# scoreboard.net
KiCad netlist of a schematic drawn in EAGLE
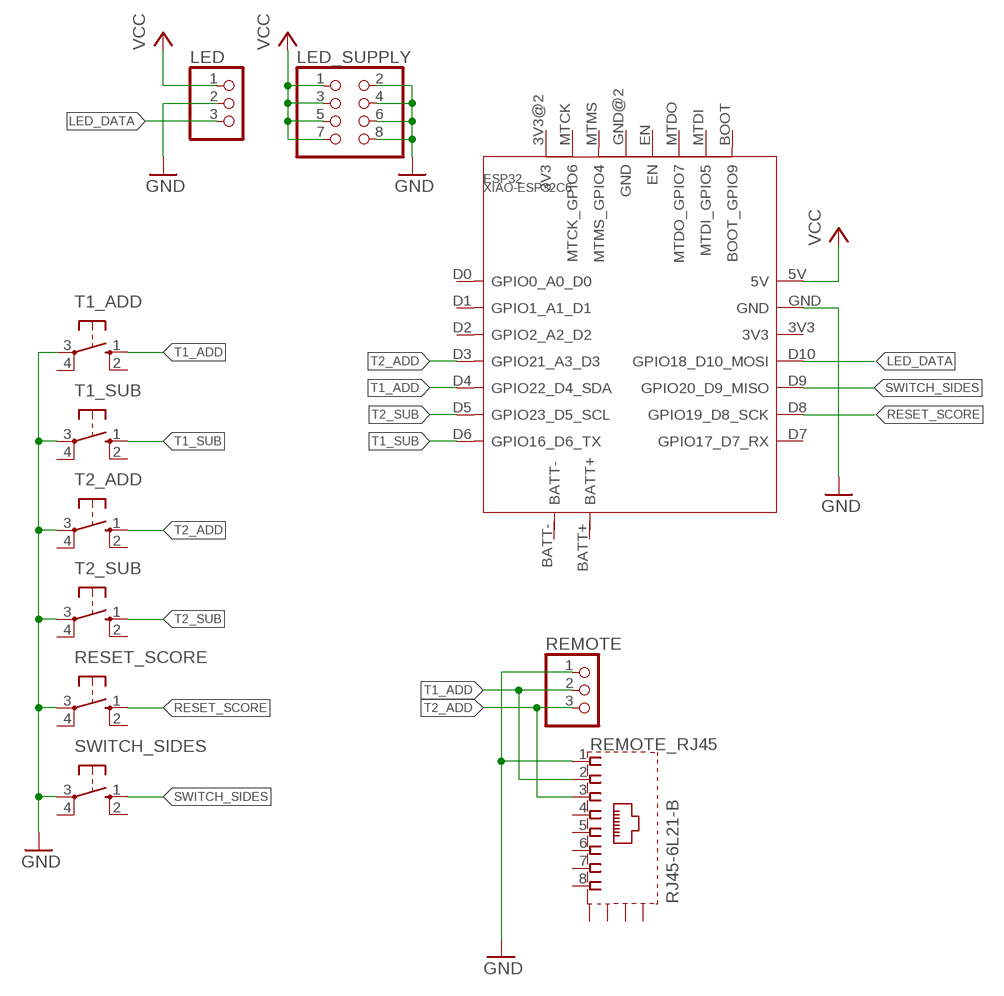
[diagram p0: schematic, sheet 1]

(export (version "E")
  (design (tool "Eeschema 10.0.6"))
  (components
    (comp (ref "ESP32")
      (value "XIAO-ESP32C6")
      (footprint "eagle-import:XIAO-ESP32C6-MODULE14P-2.54-21X17.8MM")
      (libsource (lib "eagle-import") (part "XIAO-ESP32C6"))
    )
    (comp (ref "LED")
      (value "PINHD-1X3")
      (footprint "eagle-import:1X03")
      (libsource (lib "eagle-import") (part "PINHD-1X3"))
    )
    (comp (ref "LED_SUPPLY")
      (value "PINHD-2X4")
      (footprint "eagle-import:2X04")
      (libsource (lib "eagle-import") (part "PINHD-2X4"))
    )
    (comp (ref "REMOTE")
      (value "PINHD-1X3")
      (footprint "eagle-import:1X03")
      (libsource (lib "eagle-import") (part "PINHD-1X3"))
    )
    (comp (ref "REMOTE_RJ45")
      (value "RJ45-6L21-B")
      (footprint "eagle-import:RJ45-SHIELD1")
      (libsource (lib "eagle-import") (part "RJ4521-B-6L"))
    )
    (comp (ref "RESET_SCORE")
      (value "10-XX")
      (footprint "eagle-import:B3F-10XX")
      (fields (field (name "MPN") "B3F-1000"))
      (libsource (lib "eagle-import") (part "10-XX"))
    )
    (comp (ref "SWITCH_SIDES")
      (value "10-XX")
      (footprint "eagle-import:B3F-10XX")
      (fields (field (name "MPN") "B3F-1000"))
      (libsource (lib "eagle-import") (part "10-XX"))
    )
    (comp (ref "T1_ADD")
      (value "10-XX")
      (footprint "eagle-import:B3F-10XX")
      (fields (field (name "MPN") "B3F-1000"))
      (libsource (lib "eagle-import") (part "10-XX"))
    )
    (comp (ref "T1_SUB")
      (value "10-XX")
      (footprint "eagle-import:B3F-10XX")
      (fields (field (name "MPN") "B3F-1000"))
      (libsource (lib "eagle-import") (part "10-XX"))
    )
    (comp (ref "T2_ADD")
      (value "10-XX")
      (footprint "eagle-import:B3F-10XX")
      (fields (field (name "MPN") "B3F-1000"))
      (libsource (lib "eagle-import") (part "10-XX"))
    )
    (comp (ref "T2_SUB")
      (value "10-XX")
      (footprint "eagle-import:B3F-10XX")
      (fields (field (name "MPN") "B3F-1000"))
      (libsource (lib "eagle-import") (part "10-XX"))
    )
  )
  (nets
    (net (code "1") (name "GND") (class "Default")
      (node (ref "ESP32") (pin "GND") (pinfunction "GND_GND") (pintype "bidirectional"))
      (node (ref "LED") (pin "2") (pinfunction "2_2") (pintype "passive"))
      (node (ref "LED_SUPPLY") (pin "2") (pinfunction "2_2") (pintype "passive"))
      (node (ref "LED_SUPPLY") (pin "4") (pinfunction "4_4") (pintype "passive"))
      (node (ref "LED_SUPPLY") (pin "6") (pinfunction "6_6") (pintype "passive"))
      (node (ref "LED_SUPPLY") (pin "8") (pinfunction "8_8") (pintype "passive"))
      (node (ref "REMOTE") (pin "1") (pinfunction "1_1") (pintype "passive"))
      (node (ref "REMOTE_RJ45") (pin "1") (pinfunction "1_1") (pintype "passive"))
      (node (ref "RESET_SCORE") (pin "3") (pinfunction "P_3") (pintype "passive"))
      (node (ref "SWITCH_SIDES") (pin "3") (pinfunction "P_3") (pintype "passive"))
      (node (ref "T1_ADD") (pin "3") (pinfunction "P_3") (pintype "passive"))
      (node (ref "T1_SUB") (pin "3") (pinfunction "P_3") (pintype "passive"))
      (node (ref "T2_ADD") (pin "3") (pinfunction "P_3") (pintype "passive"))
      (node (ref "T2_SUB") (pin "3") (pinfunction "P_3") (pintype "passive"))
    )
    (net (code "2") (name "LED_DATA") (class "Default")
      (node (ref "ESP32") (pin "D10") (pinfunction "GPIO18_D10_MOSI_D10") (pintype "bidirectional"))
      (node (ref "LED") (pin "3") (pinfunction "3_3") (pintype "passive"))
    )
    (net (code "3") (name "RESET_SCORE") (class "Default")
      (node (ref "ESP32") (pin "D8") (pinfunction "GPIO19_D8_SCK_D8") (pintype "bidirectional"))
      (node (ref "RESET_SCORE") (pin "1") (pinfunction "S_1") (pintype "passive"))
    )
    (net (code "4") (name "SWITCH_SIDES") (class "Default")
      (node (ref "ESP32") (pin "D9") (pinfunction "GPIO20_D9_MISO_D9") (pintype "bidirectional"))
      (node (ref "SWITCH_SIDES") (pin "1") (pinfunction "S_1") (pintype "passive"))
    )
    (net (code "5") (name "T1_ADD") (class "Default")
      (node (ref "ESP32") (pin "D4") (pinfunction "GPIO22_D4_SDA_D4") (pintype "bidirectional"))
      (node (ref "REMOTE") (pin "2") (pinfunction "2_2") (pintype "passive"))
      (node (ref "REMOTE_RJ45") (pin "2") (pinfunction "2_2") (pintype "passive"))
      (node (ref "T1_ADD") (pin "1") (pinfunction "S_1") (pintype "passive"))
    )
    (net (code "6") (name "T1_SUB") (class "Default")
      (node (ref "ESP32") (pin "D6") (pinfunction "GPIO16_D6_TX_D6") (pintype "bidirectional"))
      (node (ref "T1_SUB") (pin "1") (pinfunction "S_1") (pintype "passive"))
    )
    (net (code "7") (name "T2_ADD") (class "Default")
      (node (ref "ESP32") (pin "D3") (pinfunction "GPIO21_A3_D3_D3") (pintype "bidirectional"))
      (node (ref "REMOTE") (pin "3") (pinfunction "3_3") (pintype "passive"))
      (node (ref "REMOTE_RJ45") (pin "3") (pinfunction "3_3") (pintype "passive"))
      (node (ref "T2_ADD") (pin "1") (pinfunction "S_1") (pintype "passive"))
    )
    (net (code "8") (name "T2_SUB") (class "Default")
      (node (ref "ESP32") (pin "D5") (pinfunction "GPIO23_D5_SCL_D5") (pintype "bidirectional"))
      (node (ref "T2_SUB") (pin "1") (pinfunction "S_1") (pintype "passive"))
    )
    (net (code "9") (name "VCC") (class "Default")
      (node (ref "ESP32") (pin "5V") (pinfunction "5V_5V") (pintype "bidirectional"))
      (node (ref "LED") (pin "1") (pinfunction "1_1") (pintype "passive"))
      (node (ref "LED_SUPPLY") (pin "1") (pinfunction "1_1") (pintype "passive"))
      (node (ref "LED_SUPPLY") (pin "3") (pinfunction "3_3") (pintype "passive"))
      (node (ref "LED_SUPPLY") (pin "5") (pinfunction "5_5") (pintype "passive"))
      (node (ref "LED_SUPPLY") (pin "7") (pinfunction "7_7") (pintype "passive"))
    )
    (net (code "10") (name "unconnected-(ESP32-3V3-Pad3V3@2)") (class "Default")
      (node (ref "ESP32") (pin "3V3@2") (pinfunction "3V3_3V3@2") (pintype "bidirectional"))
    )
    (net (code "11") (name "unconnected-(ESP32-BOOT_GPIO9-PadBOOT)") (class "Default")
      (node (ref "ESP32") (pin "BOOT") (pinfunction "BOOT_GPIO9_BOOT") (pintype "bidirectional"))
    )
    (net (code "12") (name "unconnected-(ESP32-GND-PadGND@2)") (class "Default")
      (node (ref "ESP32") (pin "GND@2") (pinfunction "GND_GND@2") (pintype "bidirectional"))
    )
    (net (code "13") (name "unconnected-(ESP32-GPIO0_A0_D0-PadD0)") (class "Default")
      (node (ref "ESP32") (pin "D0") (pinfunction "GPIO0_A0_D0_D0") (pintype "bidirectional"))
    )
    (net (code "14") (name "unconnected-(ESP32-GPIO1_A1_D1-PadD1)") (class "Default")
      (node (ref "ESP32") (pin "D1") (pinfunction "GPIO1_A1_D1_D1") (pintype "bidirectional"))
    )
    (net (code "15") (name "unconnected-(ESP32-GPIO2_A2_D2-PadD2)") (class "Default")
      (node (ref "ESP32") (pin "D2") (pinfunction "GPIO2_A2_D2_D2") (pintype "bidirectional"))
    )
    (net (code "16") (name "unconnected-(ESP32-GPIO17_D7_RX-PadD7)") (class "Default")
      (node (ref "ESP32") (pin "D7") (pinfunction "GPIO17_D7_RX_D7") (pintype "bidirectional"))
    )
    (net (code "17") (name "unconnected-(ESP32-MTCK_GPIO6-PadMTCK)") (class "Default")
      (node (ref "ESP32") (pin "MTCK") (pinfunction "MTCK_GPIO6_MTCK") (pintype "bidirectional"))
    )
    (net (code "18") (name "unconnected-(ESP32-MTDI_GPIO5-PadMTDI)") (class "Default")
      (node (ref "ESP32") (pin "MTDI") (pinfunction "MTDI_GPIO5_MTDI") (pintype "bidirectional"))
    )
    (net (code "19") (name "unconnected-(ESP32-MTDO_GPIO7-PadMTDO)") (class "Default")
      (node (ref "ESP32") (pin "MTDO") (pinfunction "MTDO_GPIO7_MTDO") (pintype "bidirectional"))
    )
    (net (code "20") (name "unconnected-(ESP32-MTMS_GPIO4-PadMTMS)") (class "Default")
      (node (ref "ESP32") (pin "MTMS") (pinfunction "MTMS_GPIO4_MTMS") (pintype "bidirectional"))
    )
    (net (code "21") (name "unconnected-(ESP32-Pad3V3)") (class "Default")
      (node (ref "ESP32") (pin "3V3") (pinfunction "3V3_3V3") (pintype "bidirectional"))
    )
    (net (code "22") (name "unconnected-(ESP32-PadBATT+)") (class "Default")
      (node (ref "ESP32") (pin "BATT+") (pinfunction "BATT+_BATT+") (pintype "bidirectional"))
    )
    (net (code "23") (name "unconnected-(ESP32-PadBATT-)") (class "Default")
      (node (ref "ESP32") (pin "BATT-") (pinfunction "BATT-_BATT-") (pintype "bidirectional"))
    )
    (net (code "24") (name "unconnected-(ESP32-PadEN)") (class "Default")
      (node (ref "ESP32") (pin "EN") (pinfunction "EN_EN") (pintype "bidirectional"))
    )
    (net (code "25") (name "unconnected-(REMOTE_RJ45-Pad4)") (class "Default")
      (node (ref "REMOTE_RJ45") (pin "4") (pinfunction "4_4") (pintype "passive"))
    )
    (net (code "26") (name "unconnected-(REMOTE_RJ45-Pad5)") (class "Default")
      (node (ref "REMOTE_RJ45") (pin "5") (pinfunction "5_5") (pintype "passive"))
    )
    (net (code "27") (name "unconnected-(REMOTE_RJ45-Pad6)") (class "Default")
      (node (ref "REMOTE_RJ45") (pin "6") (pinfunction "6_6") (pintype "passive"))
    )
    (net (code "28") (name "unconnected-(REMOTE_RJ45-Pad7)") (class "Default")
      (node (ref "REMOTE_RJ45") (pin "7") (pinfunction "7_7") (pintype "passive"))
    )
    (net (code "29") (name "unconnected-(REMOTE_RJ45-Pad8)") (class "Default")
      (node (ref "REMOTE_RJ45") (pin "8") (pinfunction "8_8") (pintype "passive"))
    )
    (net (code "30") (name "unconnected-(REMOTE_RJ45-S-PadS1)") (class "Default")
      (node (ref "REMOTE_RJ45") (pin "S1") (pinfunction "S_S1") (pintype "passive"))
    )
    (net (code "31") (name "unconnected-(REMOTE_RJ45-S-PadS2)") (class "Default")
      (node (ref "REMOTE_RJ45") (pin "S2") (pinfunction "S_S2") (pintype "passive"))
    )
    (net (code "32") (name "unconnected-(REMOTE_RJ45-S-PadS3)") (class "Default")
      (node (ref "REMOTE_RJ45") (pin "S3") (pinfunction "S_S3") (pintype "passive"))
    )
    (net (code "33") (name "unconnected-(REMOTE_RJ45-S-PadS4)") (class "Default")
      (node (ref "REMOTE_RJ45") (pin "S4") (pinfunction "S_S4") (pintype "passive"))
    )
    (net (code "34") (name "unconnected-(RESET_SCORE-P1-Pad4)") (class "Default")
      (node (ref "RESET_SCORE") (pin "4") (pinfunction "P1_4") (pintype "passive"))
    )
    (net (code "35") (name "unconnected-(RESET_SCORE-S1-Pad2)") (class "Default")
      (node (ref "RESET_SCORE") (pin "2") (pinfunction "S1_2") (pintype "passive"))
    )
    (net (code "36") (name "unconnected-(SWITCH_SIDES-P1-Pad4)") (class "Default")
      (node (ref "SWITCH_SIDES") (pin "4") (pinfunction "P1_4") (pintype "passive"))
    )
    (net (code "37") (name "unconnected-(SWITCH_SIDES-S1-Pad2)") (class "Default")
      (node (ref "SWITCH_SIDES") (pin "2") (pinfunction "S1_2") (pintype "passive"))
    )
    (net (code "38") (name "unconnected-(T1_ADD-P1-Pad4)") (class "Default")
      (node (ref "T1_ADD") (pin "4") (pinfunction "P1_4") (pintype "passive"))
    )
    (net (code "39") (name "unconnected-(T1_ADD-S1-Pad2)") (class "Default")
      (node (ref "T1_ADD") (pin "2") (pinfunction "S1_2") (pintype "passive"))
    )
    (net (code "40") (name "unconnected-(T1_SUB-P1-Pad4)") (class "Default")
      (node (ref "T1_SUB") (pin "4") (pinfunction "P1_4") (pintype "passive"))
    )
    (net (code "41") (name "unconnected-(T1_SUB-S1-Pad2)") (class "Default")
      (node (ref "T1_SUB") (pin "2") (pinfunction "S1_2") (pintype "passive"))
    )
    (net (code "42") (name "unconnected-(T2_ADD-P1-Pad4)") (class "Default")
      (node (ref "T2_ADD") (pin "4") (pinfunction "P1_4") (pintype "passive"))
    )
    (net (code "43") (name "unconnected-(T2_ADD-S1-Pad2)") (class "Default")
      (node (ref "T2_ADD") (pin "2") (pinfunction "S1_2") (pintype "passive"))
    )
    (net (code "44") (name "unconnected-(T2_SUB-P1-Pad4)") (class "Default")
      (node (ref "T2_SUB") (pin "4") (pinfunction "P1_4") (pintype "passive"))
    )
    (net (code "45") (name "unconnected-(T2_SUB-S1-Pad2)") (class "Default")
      (node (ref "T2_SUB") (pin "2") (pinfunction "S1_2") (pintype "passive"))
    )
  )
)
